# Car_Circuitry.net
KiCad netlist of a schematic drawn in Altium Designer
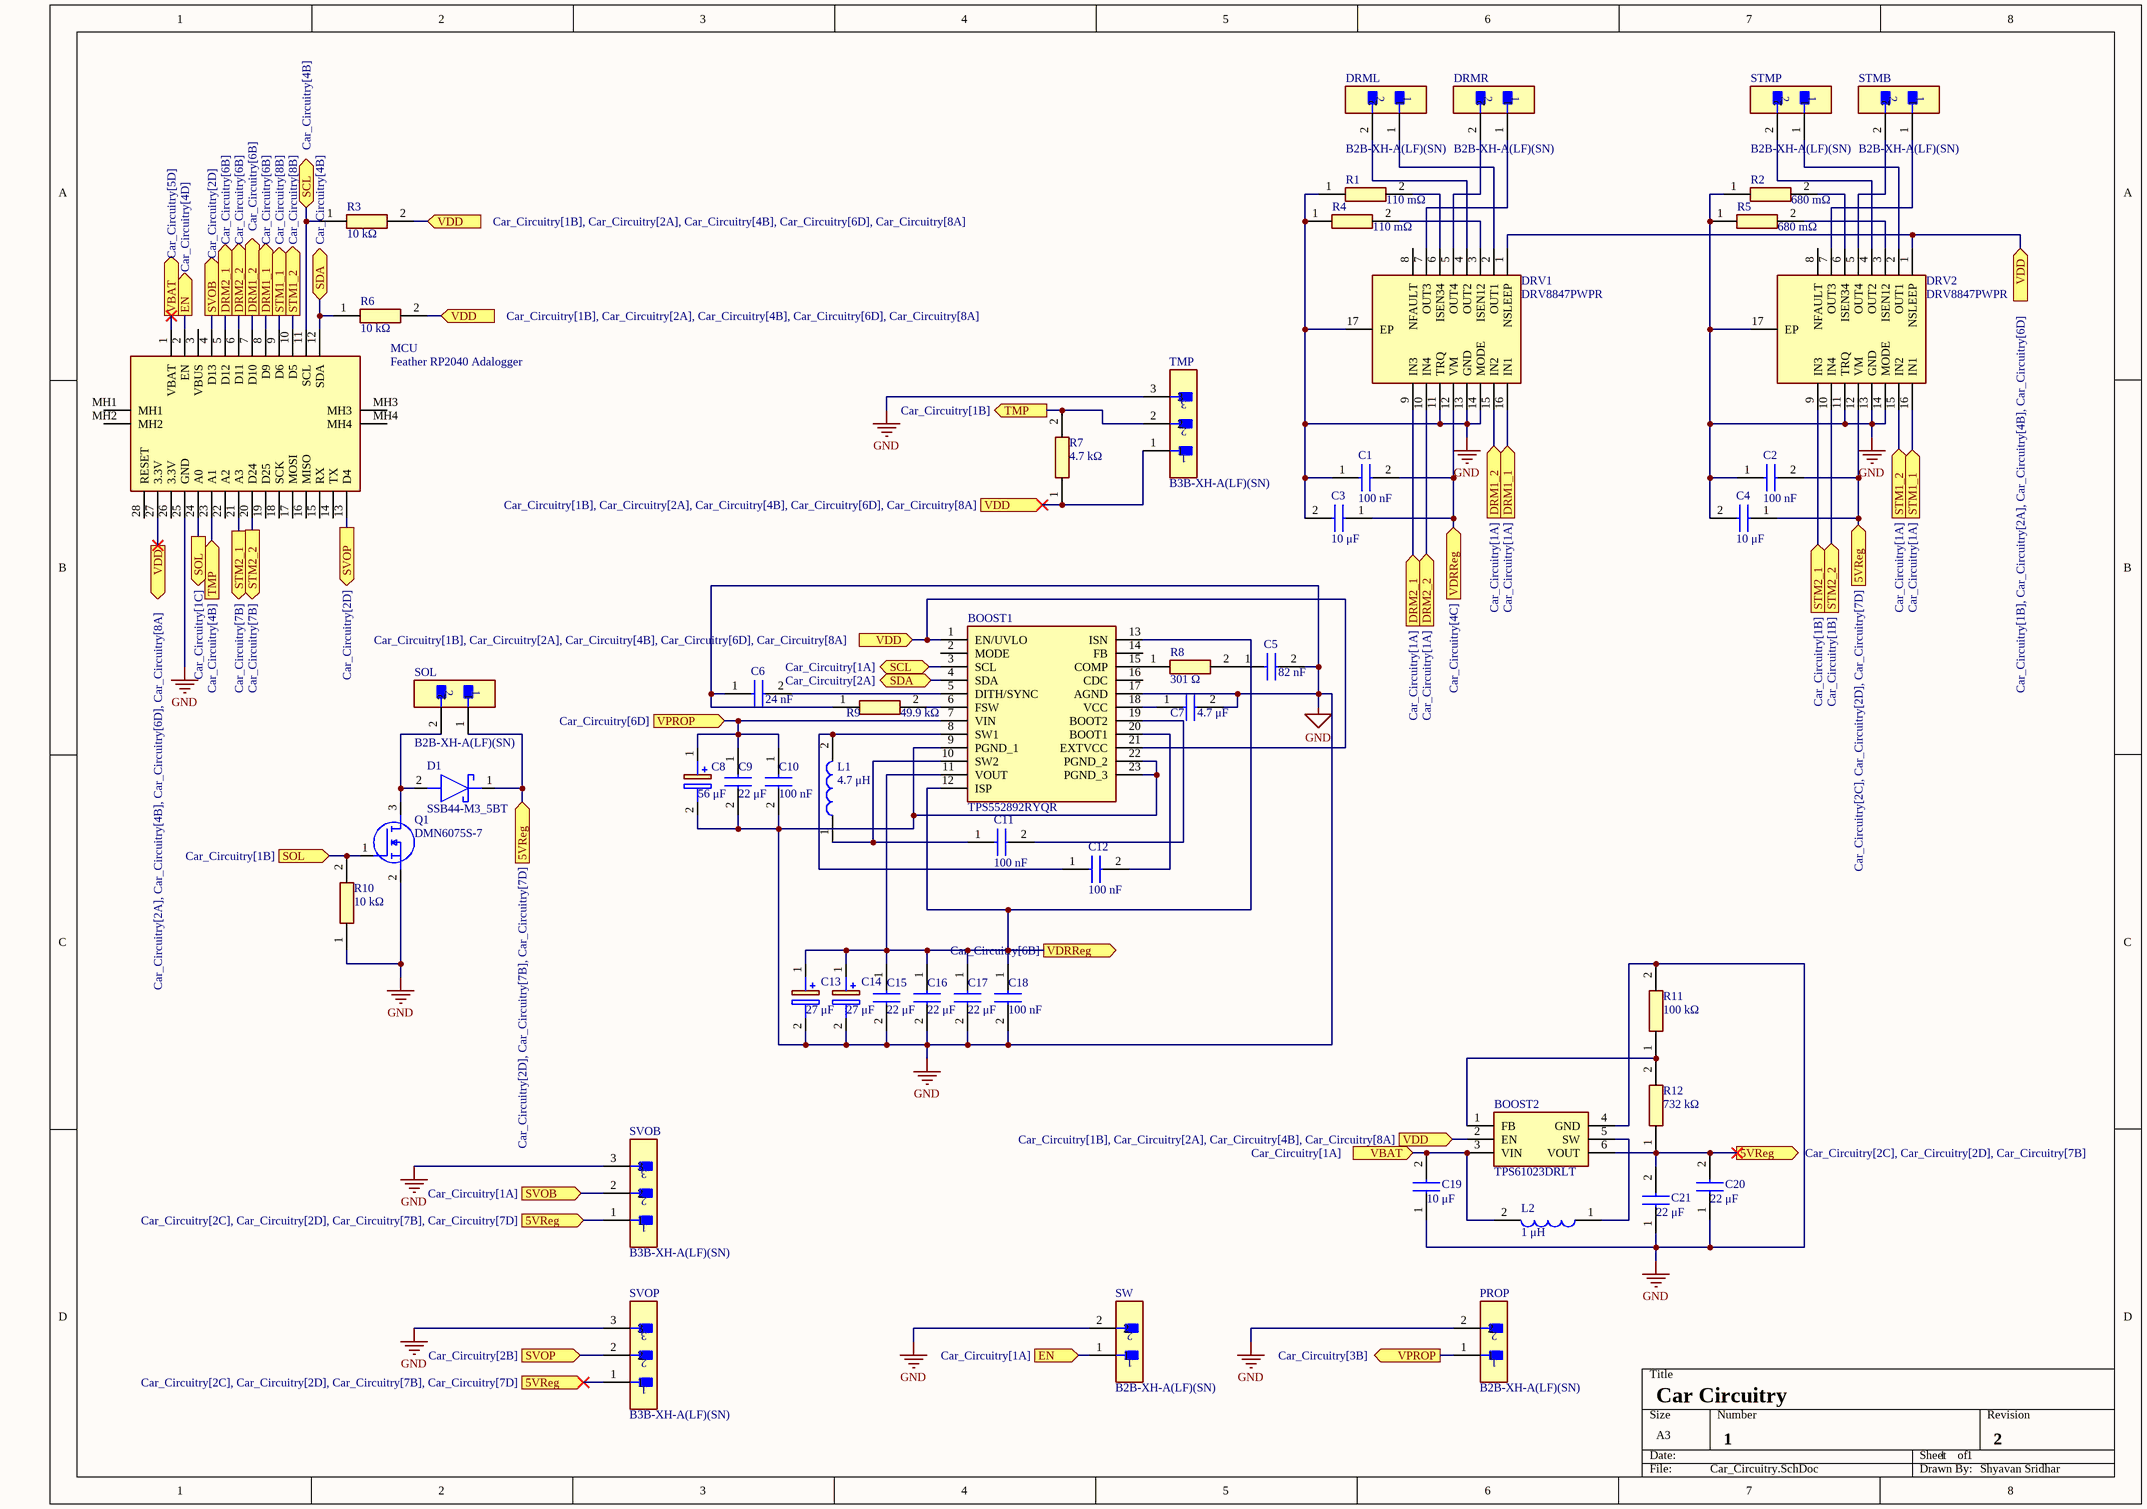
[diagram p0: Car_Circuitry.SchDoc]

(export (version "E")
  (design (tool "Eeschema 10.0.6"))
  (components
    (comp (ref "BOOST1")
      (value "TPS552892RYQR")
      (footprint "SamacSys:TPS552892RYQR")
      (description "Integrated Circuit")
      (fields (field (name "MOUSER PART NUMBER") "595-TPS552892RYQR"))
      (libsource (lib "SamacSys") (part "TPS552892RYQR"))
    )
    (comp (ref "BOOST2")
      (value "TPS61023DRLT")
      (footprint "SamacSys:SOTFL50P160X60-6N")
      (description "Integrated Circuit")
      (fields (field (name "MOUSER PART NUMBER") "595-TPS61023DRLT"))
      (libsource (lib "*") (part "TPS61023DRLT"))
    )
    (comp (ref "C1")
      (value "100 nF")
      (footprint "SamacSys:CAPC2012X95N")
      (description "Capacitor")
      (fields
        (field (name "MANUFACTURER_PART_NUMBER") "CL21B104KBCNNNC")
        (field (name "MOUSER PART NUMBER") "187-CL21B104KBCNNNC")
      )
      (libsource (lib "SamacSys") (part "CL21B104KBCNNNC"))
    )
    (comp (ref "C2")
      (value "100 nF")
      (footprint "SamacSys:CAPC2012X95N")
      (description "Capacitor")
      (fields
        (field (name "MANUFACTURER_PART_NUMBER") "CL21B104KBCNNNC")
        (field (name "MOUSER PART NUMBER") "187-CL21B104KBCNNNC")
      )
      (libsource (lib "SamacSys") (part "CL21B104KBCNNNC"))
    )
    (comp (ref "C3")
      (value "10 μF")
      (footprint "SamacSys:CAPC2012X140N")
      (description "Capacitor")
      (fields
        (field (name "MANUFACTURER_PART_NUMBER") "CL21B106KOQNNNE")
        (field (name "MOUSER PART NUMBER") "187-CL21B106KOQNNNE")
      )
      (libsource (lib "*") (part "CL21B106KOQNNNE"))
    )
    (comp (ref "C4")
      (value "10 μF")
      (footprint "SamacSys:CAPC2012X140N")
      (description "Capacitor")
      (fields
        (field (name "MANUFACTURER_PART_NUMBER") "CL21B106KOQNNNE")
        (field (name "MOUSER PART NUMBER") "187-CL21B106KOQNNNE")
      )
      (libsource (lib "*") (part "CL21B106KOQNNNE"))
    )
    (comp (ref "C5")
      (value "82 nF")
      (footprint "SamacSys:CAPC1005X55N")
      (description "Capacitor")
      (fields
        (field (name "MANUFACTURER_PART_NUMBER") "GRM155R61A823KA01D")
        (field (name "MOUSER PART NUMBER") "81-GRM155R61A823KA1D")
      )
      (libsource (lib "SamacSys") (part "GRM155R61A823KA01D"))
    )
    (comp (ref "C6")
      (value "24 nF")
      (footprint "SamacSys:CAPC2013X94N")
      (description "Capacitor")
      (fields
        (field (name "MANUFACTURER_PART_NUMBER") "08051C243JAT2A")
        (field (name "MOUSER PART NUMBER") "581-08051C243JAT2A")
      )
      (libsource (lib "*") (part "08051C243JAT2A"))
    )
    (comp (ref "C7")
      (value "4.7 μF")
      (footprint "SamacSys:CAPC1608X80N")
      (description "Capacitor")
      (fields
        (field (name "MANUFACTURER_PART_NUMBER") "C1608X6S1C475K080AC")
        (field (name "MOUSER PART NUMBER") "810-C1608X6S1C475K")
      )
      (libsource (lib "*") (part "C1608X6S1C475K080AC"))
    )
    (comp (ref "C8")
      (value "56 μF")
      (footprint "SamacSys:16SVF82M")
      (description "Capacitor Polarised")
      (fields
        (field (name "MANUFACTURER_PART_NUMBER") "20SVPF56MX")
        (field (name "MOUSER PART NUMBER") "667-20SVPF56MX")
      )
      (libsource (lib "*") (part "20SVPF56MX"))
    )
    (comp (ref "C9")
      (value "22 μF")
      (footprint "SamacSys:CAPC3225X270N")
      (description "Capacitor")
      (fields
        (field (name "MANUFACTURER_PART_NUMBER") "GRM32ER61E226KE15K")
        (field (name "MOUSER PART NUMBER") "81-GRM32ER61E226KE5K")
      )
      (libsource (lib "*") (part "GRM32ER61E226KE15K"))
    )
    (comp (ref "C10")
      (value "100 nF")
      (footprint "SamacSys:CAPC1005X55N")
      (description "Capacitor")
      (fields
        (field (name "MANUFACTURER_PART_NUMBER") "CL05B104KA5NNNC")
        (field (name "MOUSER PART NUMBER") "187-CL05B104KA5NNNC")
      )
      (libsource (lib "SamacSys") (part "CL05B104KA5NNNC"))
    )
    (comp (ref "C11")
      (value "100 nF")
      (footprint "SamacSys:CAPC1005X55N")
      (description "Capacitor")
      (fields
        (field (name "MANUFACTURER_PART_NUMBER") "CL05B104KA5NNNC")
        (field (name "MOUSER PART NUMBER") "187-CL05B104KA5NNNC")
      )
      (libsource (lib "SamacSys") (part "CL05B104KA5NNNC"))
    )
    (comp (ref "C12")
      (value "100 nF")
      (footprint "SamacSys:CAPC1005X55N")
      (description "Capacitor")
      (fields
        (field (name "MANUFACTURER_PART_NUMBER") "CL05B104KA5NNNC")
        (field (name "MOUSER PART NUMBER") "187-CL05B104KA5NNNC")
      )
      (libsource (lib "SamacSys") (part "CL05B104KA5NNNC"))
    )
    (comp (ref "C13")
      (value "27 μF")
      (footprint "SamacSys:16SVF82M")
      (description "Capacitor Polarised")
      (fields
        (field (name "MANUFACTURER_PART_NUMBER") "25SVPF27MX")
        (field (name "MOUSER PART NUMBER") "667-25SVPF27MX")
      )
      (libsource (lib "*") (part "25SVPF27MX"))
    )
    (comp (ref "C14")
      (value "27 μF")
      (footprint "SamacSys:16SVF82M")
      (description "Capacitor Polarised")
      (fields
        (field (name "MANUFACTURER_PART_NUMBER") "25SVPF27MX")
        (field (name "MOUSER PART NUMBER") "667-25SVPF27MX")
      )
      (libsource (lib "*") (part "25SVPF27MX"))
    )
    (comp (ref "C15")
      (value "22 μF")
      (footprint "SamacSys:CAPC3225X270N")
      (description "Capacitor")
      (fields
        (field (name "MANUFACTURER_PART_NUMBER") "GRM32ER61E226KE15K")
        (field (name "MOUSER PART NUMBER") "81-GRM32ER61E226KE5K")
      )
      (libsource (lib "*") (part "GRM32ER61E226KE15K"))
    )
    (comp (ref "C16")
      (value "22 μF")
      (footprint "SamacSys:CAPC3225X270N")
      (description "Capacitor")
      (fields
        (field (name "MANUFACTURER_PART_NUMBER") "GRM32ER61E226KE15K")
        (field (name "MOUSER PART NUMBER") "81-GRM32ER61E226KE5K")
      )
      (libsource (lib "*") (part "GRM32ER61E226KE15K"))
    )
    (comp (ref "C17")
      (value "22 μF")
      (footprint "SamacSys:CAPC3225X270N")
      (description "Capacitor")
      (fields
        (field (name "MANUFACTURER_PART_NUMBER") "GRM32ER61E226KE15K")
        (field (name "MOUSER PART NUMBER") "81-GRM32ER61E226KE5K")
      )
      (libsource (lib "*") (part "GRM32ER61E226KE15K"))
    )
    (comp (ref "C18")
      (value "100 nF")
      (footprint "SamacSys:CAPC1005X55N")
      (description "Capacitor")
      (fields
        (field (name "MANUFACTURER_PART_NUMBER") "CL05B104KA5NNNC")
        (field (name "MOUSER PART NUMBER") "187-CL05B104KA5NNNC")
      )
      (libsource (lib "SamacSys") (part "CL05B104KA5NNNC"))
    )
    (comp (ref "C19")
      (value "10 μF")
      (footprint "SamacSys:CAPC2012X140N")
      (description "Capacitor")
      (fields
        (field (name "MANUFACTURER_PART_NUMBER") "CL21B106KOQNNNE")
        (field (name "MOUSER PART NUMBER") "187-CL21B106KOQNNNE")
      )
      (libsource (lib "*") (part "CL21B106KOQNNNE"))
    )
    (comp (ref "C20")
      (value "22 μF")
      (footprint "SamacSys:CAPC3216X180N")
      (description "Capacitor")
      (fields
        (field (name "MANUFACTURER_PART_NUMBER") "CL31B226KPHNNNE")
        (field (name "MOUSER PART NUMBER") "187-CL31B226KPHNNNE")
      )
      (libsource (lib "*") (part "CL31B226KPHNNNE"))
    )
    (comp (ref "C21")
      (value "22 μF")
      (footprint "SamacSys:CAPC3216X180N")
      (description "Capacitor")
      (fields
        (field (name "MANUFACTURER_PART_NUMBER") "CL31B226KPHNNNE")
        (field (name "MOUSER PART NUMBER") "187-CL31B226KPHNNNE")
      )
      (libsource (lib "*") (part "CL31B226KPHNNNE"))
    )
    (comp (ref "D1")
      (value "SSB44-M3_5BT")
      (footprint "SamacSys:DIOM5436X244N")
      (description "Schottky Diode")
      (fields
        (field (name "MANUFACTURER_PART_NUMBER") "SSB44-M3/5BT")
        (field (name "MOUSER PART NUMBER") "78-SSB44-M35BT")
      )
      (libsource (lib "SamacSys") (part "SSB44-M3_5BT"))
    )
    (comp (ref "DRML")
      (value "B2B-XH-A(LF)(SN)")
      (footprint "FP-B2B-XH-A_LF_SN-MFG")
      (description "CONN HEADER VERT 2POS 2.5MM")
      (libsource (lib "") (part "3bc925449376181038e59eaffc5286c_1"))
    )
    (comp (ref "DRMR")
      (value "B2B-XH-A(LF)(SN)")
      (footprint "FP-B2B-XH-A_LF_SN-MFG")
      (description "CONN HEADER VERT 2POS 2.5MM")
      (libsource (lib "") (part "3bc925449376181038e59eaffc5286c_1"))
    )
    (comp (ref "DRV1")
      (value "DRV8847PWPR")
      (footprint "SamacSys:SOP65P640X120-17N")
      (description "Integrated Circuit")
      (fields (field (name "MOUSER PART NUMBER") "595-DRV8847PWPR"))
      (libsource (lib "SamacSys") (part "DRV8847PWPR"))
    )
    (comp (ref "DRV2")
      (value "DRV8847PWPR")
      (footprint "SamacSys:SOP65P640X120-17N")
      (description "Integrated Circuit")
      (fields (field (name "MOUSER PART NUMBER") "595-DRV8847PWPR"))
      (libsource (lib "SamacSys") (part "DRV8847PWPR"))
    )
    (comp (ref "L1")
      (value "4.7 μH")
      (footprint "SamacSys:INDPM6664X610N")
      (description "Inductor")
      (fields
        (field (name "MANUFACTURER_PART_NUMBER") "74439346047")
        (field (name "MOUSER PART NUMBER") "710-74439346047")
      )
      (libsource (lib "SamacSys") (part "74439346047"))
    )
    (comp (ref "L2")
      (value "1 μH")
      (footprint "SamacSys:74438357010")
      (description "Inductor")
      (fields
        (field (name "MANUFACTURER_PART_NUMBER") "74438357010")
        (field (name "MOUSER PART NUMBER") "710-74438357010")
      )
      (libsource (lib "*") (part "74438357010"))
    )
    (comp (ref "MCU")
      (value "Feather RP2040 Adalogger")
      (footprint "SamacSys:2796")
      (description "Adafruit Microcontroller")
      (fields (field (name "MANUFACTURER_PART_NUMBER") "4884") (field (name "MOUSER PART NUMBER") "485-5980"))
      (libsource (lib "*") (part "2796"))
    )
    (comp (ref "PROP")
      (value "B2B-XH-A(LF)(SN)")
      (footprint "FP-B2B-XH-A_LF_SN-MFG")
      (description "CONN HEADER VERT 2POS 2.5MM")
      (libsource (lib "Altium Content Vault") (part "3bc925449376181038e59eaffc5286c"))
    )
    (comp (ref "Q1")
      (value "DMN6075S-7")
      (footprint "SamacSys:SOT96P240X110-3N")
      (description "MOSFET (N-Channel)")
      (fields
        (field (name "MANUFACTURER_PART_NUMBER") "DMN6075SQ-7")
        (field (name "MOUSER PART NUMBER") "621-DMN6075SQ-7")
      )
      (libsource (lib "*") (part "DMN6075SQ-7"))
    )
    (comp (ref "R1")
      (value "110 mΩ")
      (footprint "SamacSys:ERJ6_B_BW_R_LW_CW_D")
      (description "Resistor")
      (fields
        (field (name "MANUFACTURER_PART_NUMBER") "ERJ-6DSFR11V")
        (field (name "MOUSER PART NUMBER") "667-ERJ-6DSFR11V")
      )
      (libsource (lib "SamacSys") (part "ERJ-6DSFR11V"))
    )
    (comp (ref "R2")
      (value "680 mΩ")
      (footprint "SamacSys:ERJ6_B_BW_R_LW_CW_D")
      (description "Resistor")
      (fields (field (name "MANUFACTURER_PART_NUMBER") "ERJ-6DQJR68V"))
      (libsource (lib "SamacSys") (part "ERJ-6DQJR68V"))
    )
    (comp (ref "R3")
      (value "10 kΩ")
      (footprint "SamacSys:RESC2012X70N")
      (description "Resistor")
      (fields
        (field (name "MANUFACTURER_PART_NUMBER") "ERJ-6GEYJ103V")
        (field (name "MOUSER PART NUMBER") "667-ERJ-6GEYJ103V")
      )
      (libsource (lib "*") (part "ERJ-6GEYJ103V"))
    )
    (comp (ref "R4")
      (value "110 mΩ")
      (footprint "SamacSys:ERJ6_B_BW_R_LW_CW_D")
      (description "Resistor")
      (fields
        (field (name "MANUFACTURER_PART_NUMBER") "ERJ-6DSFR11V")
        (field (name "MOUSER PART NUMBER") "667-ERJ-6DSFR11V")
      )
      (libsource (lib "SamacSys") (part "ERJ-6DSFR11V"))
    )
    (comp (ref "R5")
      (value "680 mΩ")
      (footprint "SamacSys:ERJ6_B_BW_R_LW_CW_D")
      (description "Resistor")
      (fields (field (name "MANUFACTURER_PART_NUMBER") "ERJ-6DQJR68V"))
      (libsource (lib "SamacSys") (part "ERJ-6DQJR68V"))
    )
    (comp (ref "R6")
      (value "10 kΩ")
      (footprint "SamacSys:RESC2012X70N")
      (description "Resistor")
      (fields
        (field (name "MANUFACTURER_PART_NUMBER") "ERJ-6GEYJ103V")
        (field (name "MOUSER PART NUMBER") "667-ERJ-6GEYJ103V")
      )
      (libsource (lib "*") (part "ERJ-6GEYJ103V"))
    )
    (comp (ref "R7")
      (value "4.7 kΩ")
      (footprint "SamacSys:RESAD1530W60L610D230")
      (description "Resistor")
      (fields
        (field (name "MANUFACTURER_PART_NUMBER") "CF1/4C472J")
        (field (name "MOUSER PART NUMBER") "660-CF1/4C472J")
      )
      (libsource (lib "*") (part "CF1_4C472J"))
    )
    (comp (ref "R8")
      (value "301 Ω")
      (footprint "RESC1005X40N")
      (description "Resistor")
      (fields
        (field (name "MANUFACTURER_PART_NUMBER") "CRCW0402301RFKED")
        (field (name "MOUSER PART NUMBER") "71-CRCW0402-301-E3")
      )
      (libsource (lib "SamacSys") (part "CRCW0402301RFKED"))
    )
    (comp (ref "R9")
      (value "49.9 kΩ")
      (footprint "SamacSys:ERJ2RKD1004X")
      (description "Resistor")
      (fields
        (field (name "MANUFACTURER_PART_NUMBER") "ERJ-2RKF4992X")
        (field (name "MOUSER PART NUMBER") "667-ERJ-2RKF4992X")
      )
      (libsource (lib "*") (part "ERJ-2RKF4992X"))
    )
    (comp (ref "R10")
      (value "10 kΩ")
      (footprint "SamacSys:RESC2012X70N")
      (description "Resistor")
      (fields
        (field (name "MANUFACTURER_PART_NUMBER") "ERJ-6GEYJ103V")
        (field (name "MOUSER PART NUMBER") "667-ERJ-6GEYJ103V")
      )
      (libsource (lib "") (part "ERJ-6GEYJ103V_1"))
    )
    (comp (ref "R11")
      (value "100 kΩ")
      (footprint "SamacSys:ERJ8ENF1000V")
      (description "Resistor")
      (fields
        (field (name "MANUFACTURER_PART_NUMBER") "ERJ-8ENF1003V")
        (field (name "MOUSER PART NUMBER") "667-ERJ-8ENF1003V")
      )
      (libsource (lib "*") (part "ERJ-8ENF1003V"))
    )
    (comp (ref "R12")
      (value "732 kΩ")
      (footprint "SamacSys:ERJ8ENF1000V")
      (description "Resistor")
      (fields
        (field (name "MANUFACTURER_PART_NUMBER") "ERJ-8ENF7323V")
        (field (name "MOUSER PART NUMBER") "667-ERJ-8ENF7323V")
      )
      (libsource (lib "*") (part "ERJ-8ENF7323V"))
    )
    (comp (ref "SOL")
      (value "B2B-XH-A(LF)(SN)")
      (footprint "FP-B2B-XH-A_LF_SN-MFG")
      (description "CONN HEADER VERT 2POS 2.5MM")
      (libsource (lib "") (part "3bc925449376181038e59eaffc5286c_1"))
    )
    (comp (ref "STMB")
      (value "B2B-XH-A(LF)(SN)")
      (footprint "FP-B2B-XH-A_LF_SN-MFG")
      (description "CONN HEADER VERT 2POS 2.5MM")
      (libsource (lib "") (part "3bc925449376181038e59eaffc5286c_1"))
    )
    (comp (ref "STMP")
      (value "B2B-XH-A(LF)(SN)")
      (footprint "FP-B2B-XH-A_LF_SN-MFG")
      (description "CONN HEADER VERT 2POS 2.5MM")
      (libsource (lib "") (part "3bc925449376181038e59eaffc5286c_1"))
    )
    (comp (ref "SVOB")
      (value "B3B-XH-A(LF)(SN)")
      (footprint "FP-B3B-XH-A_LF_SN-MFG")
      (description "CONN HEADER VERT 3POS 2.5MM")
      (libsource (lib "Altium Content Vault") (part "0d3f023dd272f625e17a2be33dea85f"))
    )
    (comp (ref "SVOP")
      (value "B3B-XH-A(LF)(SN)")
      (footprint "FP-B3B-XH-A_LF_SN-MFG")
      (description "CONN HEADER VERT 3POS 2.5MM")
      (libsource (lib "Altium Content Vault") (part "0d3f023dd272f625e17a2be33dea85f"))
    )
    (comp (ref "SW")
      (value "B2B-XH-A(LF)(SN)")
      (footprint "FP-B2B-XH-A_LF_SN-MFG")
      (description "CONN HEADER VERT 2POS 2.5MM")
      (libsource (lib "Altium Content Vault") (part "3bc925449376181038e59eaffc5286c"))
    )
    (comp (ref "TMP")
      (value "B3B-XH-A(LF)(SN)")
      (footprint "FP-B3B-XH-A_LF_SN-MFG")
      (description "CONN HEADER VERT 3POS 2.5MM")
      (libsource (lib "Altium Content Vault") (part "0d3f023dd272f625e17a2be33dea85f"))
    )
  )
  (nets
    (net (code "1") (name "/5VReg") (class "Default")
      (node (ref "BOOST2") (pin "6") (pinfunction "VOUT_6") (pintype "passive"))
      (node (ref "C2") (pin "2") (pinfunction "2_2") (pintype "passive"))
      (node (ref "C20") (pin "2") (pinfunction "2_2") (pintype "passive"))
      (node (ref "C21") (pin "2") (pinfunction "2_2") (pintype "passive"))
      (node (ref "C4") (pin "1") (pinfunction "1_1") (pintype "passive"))
      (node (ref "D1") (pin "1") (pinfunction "K_1") (pintype "passive"))
      (node (ref "DRV2") (pin "12") (pinfunction "VM_12") (pintype "passive"))
      (node (ref "R12") (pin "1") (pinfunction "1_1") (pintype "passive"))
      (node (ref "SOL") (pin "1") (pinfunction "1_1") (pintype "passive"))
      (node (ref "SVOB") (pin "1") (pinfunction "1_1") (pintype "passive"))
      (node (ref "SVOP") (pin "1") (pinfunction "1_1") (pintype "passive"))
    )
    (net (code "2") (name "/DRM1_1") (class "Default")
      (node (ref "DRV1") (pin "16") (pinfunction "IN1_16") (pintype "passive"))
      (node (ref "MCU") (pin "8") (pinfunction "D9_8") (pintype "passive"))
    )
    (net (code "3") (name "/DRM1_2") (class "Default")
      (node (ref "DRV1") (pin "15") (pinfunction "IN2_15") (pintype "passive"))
      (node (ref "MCU") (pin "7") (pinfunction "D10_7") (pintype "passive"))
    )
    (net (code "4") (name "/DRM2_1") (class "Default")
      (node (ref "DRV1") (pin "9") (pinfunction "IN3_9") (pintype "passive"))
      (node (ref "MCU") (pin "5") (pinfunction "D12_5") (pintype "passive"))
    )
    (net (code "5") (name "/DRM2_2") (class "Default")
      (node (ref "DRV1") (pin "10") (pinfunction "IN4_10") (pintype "passive"))
      (node (ref "MCU") (pin "6") (pinfunction "D11_6") (pintype "passive"))
    )
    (net (code "6") (name "/EN") (class "Default")
      (node (ref "MCU") (pin "2") (pinfunction "EN_2") (pintype "passive"))
      (node (ref "SW") (pin "1") (pinfunction "1_1") (pintype "passive"))
    )
    (net (code "7") (name "/SCL") (class "Default")
      (node (ref "BOOST1") (pin "3") (pinfunction "SCL_3") (pintype "passive"))
      (node (ref "MCU") (pin "11") (pinfunction "SCL_11") (pintype "passive"))
      (node (ref "R3") (pin "1") (pinfunction "1_1") (pintype "passive"))
    )
    (net (code "8") (name "/SDA") (class "Default")
      (node (ref "BOOST1") (pin "4") (pinfunction "SDA_4") (pintype "passive"))
      (node (ref "MCU") (pin "12") (pinfunction "SDA_12") (pintype "passive"))
      (node (ref "R6") (pin "1") (pinfunction "1_1") (pintype "passive"))
    )
    (net (code "9") (name "/SOL") (class "Default")
      (node (ref "MCU") (pin "24") (pinfunction "A0_24") (pintype "passive"))
      (node (ref "Q1") (pin "1") (pinfunction "G_1") (pintype "passive"))
      (node (ref "R10") (pin "2") (pinfunction "2_2") (pintype "passive"))
    )
    (net (code "10") (name "/STM1_1") (class "Default")
      (node (ref "DRV2") (pin "16") (pinfunction "IN1_16") (pintype "passive"))
      (node (ref "MCU") (pin "9") (pinfunction "D6_9") (pintype "passive"))
    )
    (net (code "11") (name "/STM1_2") (class "Default")
      (node (ref "DRV2") (pin "15") (pinfunction "IN2_15") (pintype "passive"))
      (node (ref "MCU") (pin "10") (pinfunction "D5_10") (pintype "passive"))
    )
    (net (code "12") (name "/STM2_1") (class "Default")
      (node (ref "DRV2") (pin "9") (pinfunction "IN3_9") (pintype "passive"))
      (node (ref "MCU") (pin "21") (pinfunction "A3_21") (pintype "passive"))
    )
    (net (code "13") (name "/STM2_2") (class "Default")
      (node (ref "DRV2") (pin "10") (pinfunction "IN4_10") (pintype "passive"))
      (node (ref "MCU") (pin "20") (pinfunction "D24_20") (pintype "passive"))
    )
    (net (code "14") (name "/SVOB") (class "Default")
      (node (ref "MCU") (pin "4") (pinfunction "D13_4") (pintype "passive"))
      (node (ref "SVOB") (pin "2") (pinfunction "2_2") (pintype "passive"))
    )
    (net (code "15") (name "/SVOP") (class "Default")
      (node (ref "MCU") (pin "13") (pinfunction "D4_13") (pintype "passive"))
      (node (ref "SVOP") (pin "2") (pinfunction "2_2") (pintype "passive"))
    )
    (net (code "16") (name "/TMP") (class "Default")
      (node (ref "MCU") (pin "23") (pinfunction "A1_23") (pintype "passive"))
      (node (ref "R7") (pin "2") (pinfunction "2_2") (pintype "passive"))
      (node (ref "TMP") (pin "2") (pinfunction "2_2") (pintype "passive"))
    )
    (net (code "17") (name "/VBAT") (class "Default")
      (node (ref "BOOST2") (pin "3") (pinfunction "VIN_3") (pintype "passive"))
      (node (ref "C19") (pin "2") (pinfunction "2_2") (pintype "passive"))
      (node (ref "L2") (pin "2") (pinfunction "2_2") (pintype "passive"))
      (node (ref "MCU") (pin "1") (pinfunction "VBAT_1") (pintype "passive"))
    )
    (net (code "18") (name "/VDD") (class "Default")
      (node (ref "BOOST1") (pin "1") (pinfunction "EN/UVLO_1") (pintype "passive"))
      (node (ref "BOOST1") (pin "21") (pinfunction "EXTVCC_21") (pintype "passive"))
      (node (ref "BOOST2") (pin "2") (pinfunction "EN_2") (pintype "passive"))
      (node (ref "DRV1") (pin "1") (pinfunction "NSLEEP_1") (pintype "passive"))
      (node (ref "DRV2") (pin "1") (pinfunction "NSLEEP_1") (pintype "passive"))
      (node (ref "MCU") (pin "27") (pinfunction "3.3V_27") (pintype "passive"))
      (node (ref "R3") (pin "2") (pinfunction "2_2") (pintype "passive"))
      (node (ref "R6") (pin "2") (pinfunction "2_2") (pintype "passive"))
      (node (ref "R7") (pin "1") (pinfunction "1_1") (pintype "passive"))
      (node (ref "TMP") (pin "1") (pinfunction "1_1") (pintype "passive"))
    )
    (net (code "19") (name "/VDRReg") (class "Default")
      (node (ref "BOOST1") (pin "11") (pinfunction "VOUT_11") (pintype "passive"))
      (node (ref "BOOST1") (pin "12") (pinfunction "ISP_12") (pintype "passive"))
      (node (ref "BOOST1") (pin "13") (pinfunction "ISN_13") (pintype "passive"))
      (node (ref "C1") (pin "2") (pinfunction "2_2") (pintype "passive"))
      (node (ref "C13") (pin "1") (pinfunction "+_1") (pintype "passive"))
      (node (ref "C14") (pin "1") (pinfunction "+_1") (pintype "passive"))
      (node (ref "C15") (pin "1") (pinfunction "1_1") (pintype "passive"))
      (node (ref "C16") (pin "1") (pinfunction "1_1") (pintype "passive"))
      (node (ref "C17") (pin "1") (pinfunction "1_1") (pintype "passive"))
      (node (ref "C18") (pin "1") (pinfunction "1_1") (pintype "passive"))
      (node (ref "C3") (pin "1") (pinfunction "1_1") (pintype "passive"))
      (node (ref "DRV1") (pin "12") (pinfunction "VM_12") (pintype "passive"))
    )
    (net (code "20") (name "/VPROP") (class "Default")
      (node (ref "BOOST1") (pin "7") (pinfunction "VIN_7") (pintype "passive"))
      (node (ref "C10") (pin "1") (pinfunction "1_1") (pintype "passive"))
      (node (ref "C8") (pin "1") (pinfunction "+_1") (pintype "passive"))
      (node (ref "C9") (pin "1") (pinfunction "1_1") (pintype "passive"))
      (node (ref "PROP") (pin "1") (pinfunction "1_1") (pintype "passive"))
    )
    (net (code "21") (name "GND") (class "Default")
      (node (ref "BOOST1") (pin "17") (pinfunction "AGND_17") (pintype "passive"))
      (node (ref "BOOST1") (pin "22") (pinfunction "PGND_2_22") (pintype "passive"))
      (node (ref "BOOST1") (pin "23") (pinfunction "PGND_3_23") (pintype "passive"))
      (node (ref "BOOST1") (pin "9") (pinfunction "PGND_1_9") (pintype "passive"))
      (node (ref "BOOST2") (pin "4") (pinfunction "GND_4") (pintype "passive"))
      (node (ref "C1") (pin "1") (pinfunction "1_1") (pintype "passive"))
      (node (ref "C10") (pin "2") (pinfunction "2_2") (pintype "passive"))
      (node (ref "C13") (pin "2") (pinfunction "-_2") (pintype "passive"))
      (node (ref "C14") (pin "2") (pinfunction "-_2") (pintype "passive"))
      (node (ref "C15") (pin "2") (pinfunction "2_2") (pintype "passive"))
      (node (ref "C16") (pin "2") (pinfunction "2_2") (pintype "passive"))
      (node (ref "C17") (pin "2") (pinfunction "2_2") (pintype "passive"))
      (node (ref "C18") (pin "2") (pinfunction "2_2") (pintype "passive"))
      (node (ref "C19") (pin "1") (pinfunction "1_1") (pintype "passive"))
      (node (ref "C2") (pin "1") (pinfunction "1_1") (pintype "passive"))
      (node (ref "C20") (pin "1") (pinfunction "1_1") (pintype "passive"))
      (node (ref "C21") (pin "1") (pinfunction "1_1") (pintype "passive"))
      (node (ref "C3") (pin "2") (pinfunction "2_2") (pintype "passive"))
      (node (ref "C4") (pin "2") (pinfunction "2_2") (pintype "passive"))
      (node (ref "C5") (pin "2") (pinfunction "2_2") (pintype "passive"))
      (node (ref "C6") (pin "1") (pinfunction "C1_1") (pintype "passive"))
      (node (ref "C7") (pin "2") (pinfunction "2_2") (pintype "passive"))
      (node (ref "C8") (pin "2") (pinfunction "-_2") (pintype "passive"))
      (node (ref "C9") (pin "2") (pinfunction "2_2") (pintype "passive"))
      (node (ref "DRV1") (pin "11") (pinfunction "TRQ_11") (pintype "passive"))
      (node (ref "DRV1") (pin "13") (pinfunction "GND_13") (pintype "passive"))
      (node (ref "DRV1") (pin "14") (pinfunction "MODE_14") (pintype "passive"))
      (node (ref "DRV1") (pin "17") (pinfunction "EP_17") (pintype "passive"))
      (node (ref "DRV2") (pin "11") (pinfunction "TRQ_11") (pintype "passive"))
      (node (ref "DRV2") (pin "13") (pinfunction "GND_13") (pintype "passive"))
      (node (ref "DRV2") (pin "14") (pinfunction "MODE_14") (pintype "passive"))
      (node (ref "DRV2") (pin "17") (pinfunction "EP_17") (pintype "passive"))
      (node (ref "MCU") (pin "25") (pinfunction "GND_25") (pintype "passive"))
      (node (ref "PROP") (pin "2") (pinfunction "2_2") (pintype "passive"))
      (node (ref "Q1") (pin "2") (pinfunction "S_2") (pintype "passive"))
      (node (ref "R1") (pin "1") (pinfunction "1_1") (pintype "passive"))
      (node (ref "R10") (pin "1") (pinfunction "1_1") (pintype "passive"))
      (node (ref "R11") (pin "2") (pinfunction "2_2") (pintype "passive"))
      (node (ref "R2") (pin "1") (pinfunction "1_1") (pintype "passive"))
      (node (ref "R4") (pin "1") (pinfunction "1_1") (pintype "passive"))
      (node (ref "R5") (pin "1") (pinfunction "1_1") (pintype "passive"))
      (node (ref "R9") (pin "1") (pinfunction "1_1") (pintype "passive"))
      (node (ref "SVOB") (pin "3") (pinfunction "3_3") (pintype "passive"))
      (node (ref "SVOP") (pin "3") (pinfunction "3_3") (pintype "passive"))
      (node (ref "SW") (pin "2") (pinfunction "2_2") (pintype "passive"))
      (node (ref "TMP") (pin "3") (pinfunction "3_3") (pintype "passive"))
    )
    (net (code "22") (name "Net-(BOOST1-BOOT1)") (class "Default")
      (node (ref "BOOST1") (pin "20") (pinfunction "BOOT1_20") (pintype "passive"))
      (node (ref "C12") (pin "2") (pinfunction "2_2") (pintype "passive"))
    )
    (net (code "23") (name "Net-(BOOST1-BOOT2)") (class "Default")
      (node (ref "BOOST1") (pin "19") (pinfunction "BOOT2_19") (pintype "passive"))
      (node (ref "C11") (pin "2") (pinfunction "2_2") (pintype "passive"))
    )
    (net (code "24") (name "Net-(BOOST1-COMP)") (class "Default")
      (node (ref "BOOST1") (pin "15") (pinfunction "COMP_15") (pintype "passive"))
      (node (ref "R8") (pin "1") (pinfunction "1_1") (pintype "passive"))
    )
    (net (code "25") (name "Net-(BOOST1-DITH{slash}SYNC)") (class "Default")
      (node (ref "BOOST1") (pin "5") (pinfunction "DITH/SYNC_5") (pintype "passive"))
      (node (ref "C6") (pin "2") (pinfunction "C2_2") (pintype "passive"))
    )
    (net (code "26") (name "Net-(BOOST1-FSW)") (class "Default")
      (node (ref "BOOST1") (pin "6") (pinfunction "FSW_6") (pintype "passive"))
      (node (ref "R9") (pin "2") (pinfunction "2_2") (pintype "passive"))
    )
    (net (code "27") (name "Net-(BOOST1-SW1)") (class "Default")
      (node (ref "BOOST1") (pin "8") (pinfunction "SW1_8") (pintype "passive"))
      (node (ref "C12") (pin "1") (pinfunction "1_1") (pintype "passive"))
      (node (ref "L1") (pin "2") (pinfunction "2_2") (pintype "passive"))
    )
    (net (code "28") (name "Net-(BOOST1-SW2)") (class "Default")
      (node (ref "BOOST1") (pin "10") (pinfunction "SW2_10") (pintype "passive"))
      (node (ref "C11") (pin "1") (pinfunction "1_1") (pintype "passive"))
      (node (ref "L1") (pin "1") (pinfunction "1_1") (pintype "passive"))
    )
    (net (code "29") (name "Net-(BOOST1-VCC)") (class "Default")
      (node (ref "BOOST1") (pin "18") (pinfunction "VCC_18") (pintype "passive"))
      (node (ref "C7") (pin "1") (pinfunction "1_1") (pintype "passive"))
    )
    (net (code "30") (name "Net-(BOOST2-FB)") (class "Default")
      (node (ref "BOOST2") (pin "1") (pinfunction "FB_1") (pintype "passive"))
      (node (ref "R11") (pin "1") (pinfunction "1_1") (pintype "passive"))
      (node (ref "R12") (pin "2") (pinfunction "2_2") (pintype "passive"))
    )
    (net (code "31") (name "Net-(BOOST2-SW)") (class "Default")
      (node (ref "BOOST2") (pin "5") (pinfunction "SW_5") (pintype "passive"))
      (node (ref "L2") (pin "1") (pinfunction "1_1") (pintype "passive"))
    )
    (net (code "32") (name "Net-(C5-Pad1)") (class "Default")
      (node (ref "C5") (pin "1") (pinfunction "1_1") (pintype "passive"))
      (node (ref "R8") (pin "2") (pinfunction "2_2") (pintype "passive"))
    )
    (net (code "33") (name "Net-(D1-A)") (class "Default")
      (node (ref "D1") (pin "2") (pinfunction "A_2") (pintype "passive"))
      (node (ref "Q1") (pin "3") (pinfunction "D_3") (pintype "passive"))
      (node (ref "SOL") (pin "2") (pinfunction "2_2") (pintype "passive"))
    )
    (net (code "34") (name "Net-(DRV1-ISEN12)") (class "Default")
      (node (ref "DRV1") (pin "3") (pinfunction "ISEN12_3") (pintype "passive"))
      (node (ref "R4") (pin "2") (pinfunction "2_2") (pintype "passive"))
    )
    (net (code "35") (name "Net-(DRV1-ISEN34)") (class "Default")
      (node (ref "DRV1") (pin "6") (pinfunction "ISEN34_6") (pintype "passive"))
      (node (ref "R1") (pin "2") (pinfunction "2_2") (pintype "passive"))
    )
    (net (code "36") (name "Net-(DRV1-OUT1)") (class "Default")
      (node (ref "DRML") (pin "1") (pinfunction "1_1") (pintype "passive"))
      (node (ref "DRV1") (pin "2") (pinfunction "OUT1_2") (pintype "passive"))
    )
    (net (code "37") (name "Net-(DRV1-OUT2)") (class "Default")
      (node (ref "DRML") (pin "2") (pinfunction "2_2") (pintype "passive"))
      (node (ref "DRV1") (pin "4") (pinfunction "OUT2_4") (pintype "passive"))
    )
    (net (code "38") (name "Net-(DRV1-OUT3)") (class "Default")
      (node (ref "DRMR") (pin "1") (pinfunction "1_1") (pintype "passive"))
      (node (ref "DRV1") (pin "7") (pinfunction "OUT3_7") (pintype "passive"))
    )
    (net (code "39") (name "Net-(DRV1-OUT4)") (class "Default")
      (node (ref "DRMR") (pin "2") (pinfunction "2_2") (pintype "passive"))
      (node (ref "DRV1") (pin "5") (pinfunction "OUT4_5") (pintype "passive"))
    )
    (net (code "40") (name "Net-(DRV2-ISEN12)") (class "Default")
      (node (ref "DRV2") (pin "3") (pinfunction "ISEN12_3") (pintype "passive"))
      (node (ref "R5") (pin "2") (pinfunction "2_2") (pintype "passive"))
    )
    (net (code "41") (name "Net-(DRV2-ISEN34)") (class "Default")
      (node (ref "DRV2") (pin "6") (pinfunction "ISEN34_6") (pintype "passive"))
      (node (ref "R2") (pin "2") (pinfunction "2_2") (pintype "passive"))
    )
    (net (code "42") (name "Net-(DRV2-OUT1)") (class "Default")
      (node (ref "DRV2") (pin "2") (pinfunction "OUT1_2") (pintype "passive"))
      (node (ref "STMP") (pin "1") (pinfunction "1_1") (pintype "passive"))
    )
    (net (code "43") (name "Net-(DRV2-OUT2)") (class "Default")
      (node (ref "DRV2") (pin "4") (pinfunction "OUT2_4") (pintype "passive"))
      (node (ref "STMP") (pin "2") (pinfunction "2_2") (pintype "passive"))
    )
    (net (code "44") (name "Net-(DRV2-OUT3)") (class "Default")
      (node (ref "DRV2") (pin "7") (pinfunction "OUT3_7") (pintype "passive"))
      (node (ref "STMB") (pin "1") (pinfunction "1_1") (pintype "passive"))
    )
    (net (code "45") (name "Net-(DRV2-OUT4)") (class "Default")
      (node (ref "DRV2") (pin "5") (pinfunction "OUT4_5") (pintype "passive"))
      (node (ref "STMB") (pin "2") (pinfunction "2_2") (pintype "passive"))
    )
    (net (code "46") (name "unconnected-(BOOST1-CDC-Pad16)") (class "Default")
      (node (ref "BOOST1") (pin "16") (pinfunction "CDC_16") (pintype "passive"))
    )
    (net (code "47") (name "unconnected-(BOOST1-FB-Pad14)") (class "Default")
      (node (ref "BOOST1") (pin "14") (pinfunction "FB_14") (pintype "passive"))
    )
    (net (code "48") (name "unconnected-(BOOST1-MODE-Pad2)") (class "Default")
      (node (ref "BOOST1") (pin "2") (pinfunction "MODE_2") (pintype "passive"))
    )
    (net (code "49") (name "unconnected-(DRV1-NFAULT-Pad8)") (class "Default")
      (node (ref "DRV1") (pin "8") (pinfunction "NFAULT_8") (pintype "passive"))
    )
    (net (code "50") (name "unconnected-(DRV2-NFAULT-Pad8)") (class "Default")
      (node (ref "DRV2") (pin "8") (pinfunction "NFAULT_8") (pintype "passive"))
    )
    (net (code "51") (name "unconnected-(MCU-3.3V-Pad26)") (class "Default")
      (node (ref "MCU") (pin "26") (pinfunction "3.3V_26") (pintype "passive"))
    )
    (net (code "52") (name "unconnected-(MCU-A2-Pad22)") (class "Default")
      (node (ref "MCU") (pin "22") (pinfunction "A2_22") (pintype "passive"))
    )
    (net (code "53") (name "unconnected-(MCU-D25-Pad19)") (class "Default")
      (node (ref "MCU") (pin "19") (pinfunction "D25_19") (pintype "passive"))
    )
    (net (code "54") (name "unconnected-(MCU-MISO-Pad16)") (class "Default")
      (node (ref "MCU") (pin "16") (pinfunction "MISO_16") (pintype "passive"))
    )
    (net (code "55") (name "unconnected-(MCU-MOSI-Pad17)") (class "Default")
      (node (ref "MCU") (pin "17") (pinfunction "MOSI_17") (pintype "passive"))
    )
    (net (code "56") (name "unconnected-(MCU-PadMH1)") (class "Default")
      (node (ref "MCU") (pin "MH1") (pinfunction "MH1_MH1") (pintype "passive"))
    )
    (net (code "57") (name "unconnected-(MCU-PadMH2)") (class "Default")
      (node (ref "MCU") (pin "MH2") (pinfunction "MH2_MH2") (pintype "passive"))
    )
    (net (code "58") (name "unconnected-(MCU-PadMH3)") (class "Default")
      (node (ref "MCU") (pin "MH3") (pinfunction "MH3_MH3") (pintype "passive"))
    )
    (net (code "59") (name "unconnected-(MCU-PadMH4)") (class "Default")
      (node (ref "MCU") (pin "MH4") (pinfunction "MH4_MH4") (pintype "passive"))
    )
    (net (code "60") (name "unconnected-(MCU-RESET-Pad28)") (class "Default")
      (node (ref "MCU") (pin "28") (pinfunction "RESET_28") (pintype "passive"))
    )
    (net (code "61") (name "unconnected-(MCU-RX-Pad15)") (class "Default")
      (node (ref "MCU") (pin "15") (pinfunction "RX_15") (pintype "passive"))
    )
    (net (code "62") (name "unconnected-(MCU-SCK-Pad18)") (class "Default")
      (node (ref "MCU") (pin "18") (pinfunction "SCK_18") (pintype "passive"))
    )
    (net (code "63") (name "unconnected-(MCU-TX-Pad14)") (class "Default")
      (node (ref "MCU") (pin "14") (pinfunction "TX_14") (pintype "passive"))
    )
    (net (code "64") (name "unconnected-(MCU-VBUS-Pad3)") (class "Default")
      (node (ref "MCU") (pin "3") (pinfunction "VBUS_3") (pintype "passive"))
    )
  )
)
